# Power_MCU.net
KiCad netlist of a schematic drawn in Altium Designer
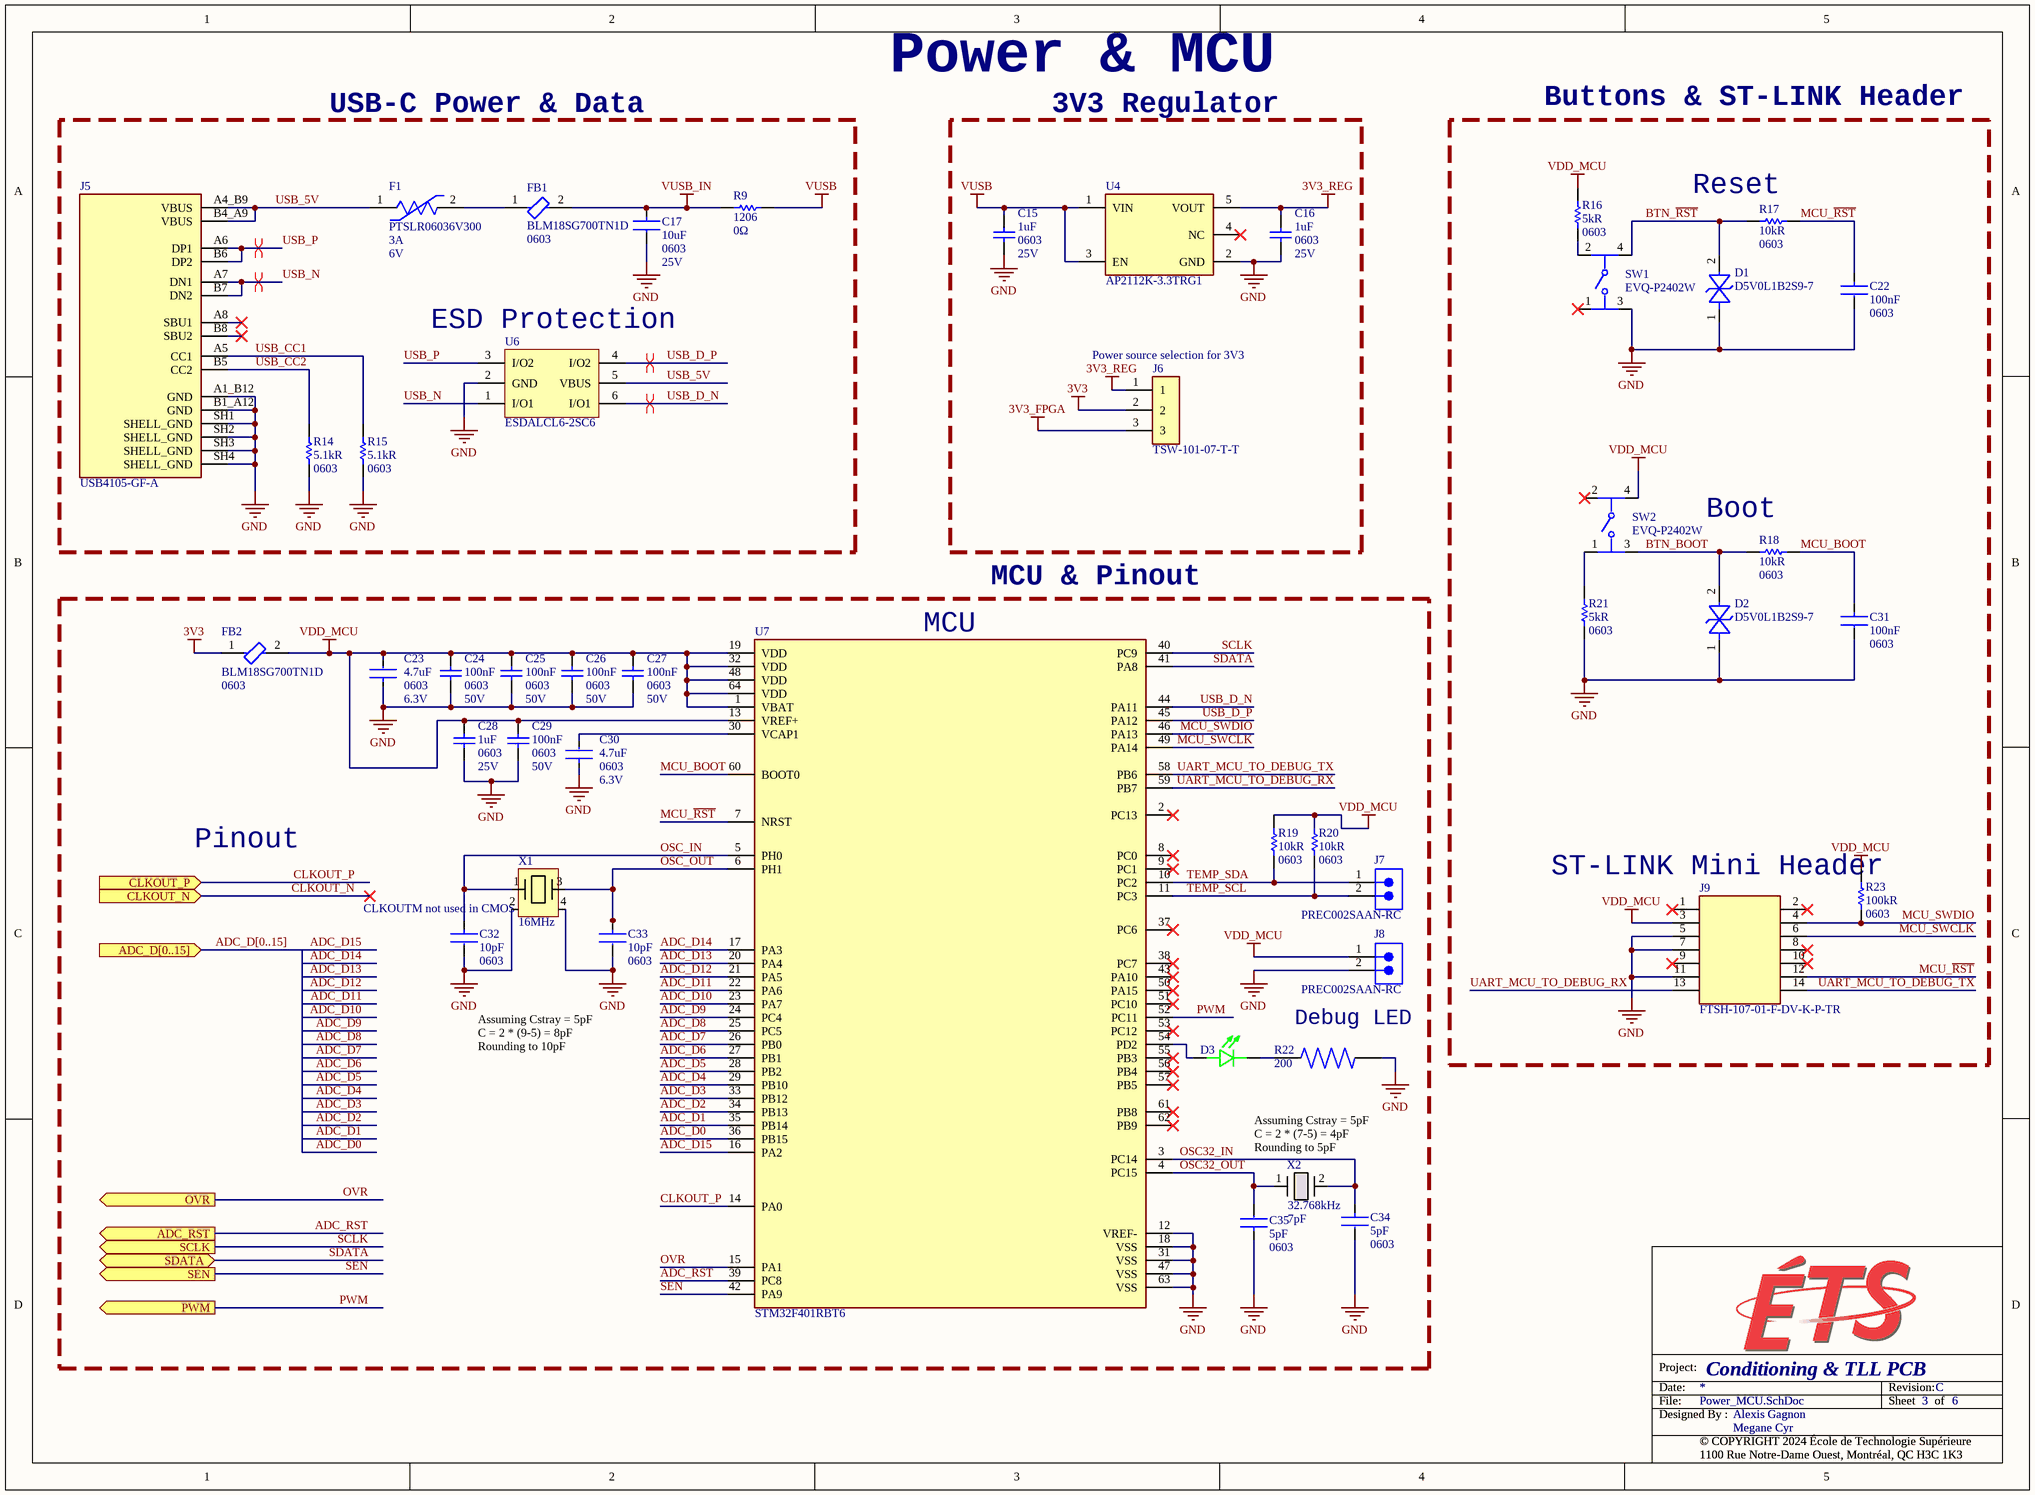
[diagram p0: Power_MCU.SchDoc]

(export (version "E")
  (design (tool "Eeschema 10.0.6"))
  (components
    (comp (ref "C15")
      (value "1uF")
      (footprint "ANTC1608X90N")
      (description "CAP CER 1UF 25V X5R 0603")
      (fields
        (field (name "MANUFACTURER") "Samsung")
        (field (name "MANUFACTURER PART NUMBER") "CL10A105KA8NNNC")
        (field (name "CASE/PACKAGE") "0603")
        (field (name "RATED DC VOLTAGE (URDC)") "25V")
      )
      (libsource (lib "ETS_Library") (part "CL10A105KA8NNNC"))
    )
    (comp (ref "C16")
      (value "1uF")
      (footprint "ANTC1608X90N")
      (description "CAP CER 1UF 25V X5R 0603")
      (fields
        (field (name "MANUFACTURER") "Samsung")
        (field (name "MANUFACTURER PART NUMBER") "CL10A105KA8NNNC")
        (field (name "CASE/PACKAGE") "0603")
        (field (name "RATED DC VOLTAGE (URDC)") "25V")
      )
      (libsource (lib "ETS_Library") (part "CL10A105KA8NNNC"))
    )
    (comp (ref "C17")
      (value "10uF")
      (footprint "BMS:C0603")
      (description "CAP CER 10UF 25V X5R 0603")
      (fields
        (field (name "TOLERANCE") "20%")
        (field (name "MANUFACTURER") "Murata")
        (field (name "CASE/PACKAGE") "0603")
        (field (name "VOLTAGE") "25V")
      )
      (libsource (lib "BMS") (part "GRM188R61E106MA73D"))
    )
    (comp (ref "C22")
      (value "100nF")
      (footprint "BMS:C0603-V2")
      (description "CAP CER 100NF 100V X8L 0603")
      (fields
        (field (name "MANUFACTURER") "Samsung")
        (field (name "MANUFACTURER PART NUMBER") "CL10E104KC8VPNC")
        (field (name "CASE") "0603")
      )
      (libsource (lib "BMS") (part "CL10E104KC8VPNC"))
    )
    (comp (ref "C23")
      (value "4.7uF")
      (footprint "FP-C0603-CG-IPC_B")
      (description "CAP CER 4.7UF 6.3V X5R 0603")
      (fields
        (field (name "PACKAGE") "0603")
        (field (name "TOLERANCE") "10%")
        (field (name "MANUFACTURER") "Kemet")
        (field (name "VOLTAGE RATING") "6.3V")
      )
      (libsource (lib "ETS_Library") (part "CMP-2006-02256-2"))
    )
    (comp (ref "C24")
      (value "100nF")
      (footprint "ANTC1608X90N")
      (description "CAP CER 0.1UF 50V X7R 0603")
      (fields
        (field (name "MANUFACTURER") "Samsung")
        (field (name "MANUFACTURER PART NUMBER") "CL10B104KB8NNWC")
        (field (name "CASE/PACKAGE") "0603")
        (field (name "VOLTAGE RATING") "50V")
      )
      (libsource (lib "ETS_Library") (part "CL10B104KB8NNWC"))
    )
    (comp (ref "C25")
      (value "100nF")
      (footprint "ANTC1608X90N")
      (description "CAP CER 0.1UF 50V X7R 0603")
      (fields
        (field (name "MANUFACTURER") "Samsung")
        (field (name "MANUFACTURER PART NUMBER") "CL10B104KB8NNWC")
        (field (name "CASE/PACKAGE") "0603")
        (field (name "VOLTAGE RATING") "50V")
      )
      (libsource (lib "ETS_Library") (part "CL10B104KB8NNWC"))
    )
    (comp (ref "C26")
      (value "100nF")
      (footprint "ANTC1608X90N")
      (description "CAP CER 0.1UF 50V X7R 0603")
      (fields
        (field (name "MANUFACTURER") "Samsung")
        (field (name "MANUFACTURER PART NUMBER") "CL10B104KB8NNWC")
        (field (name "CASE/PACKAGE") "0603")
        (field (name "VOLTAGE RATING") "50V")
      )
      (libsource (lib "ETS_Library") (part "CL10B104KB8NNWC"))
    )
    (comp (ref "C27")
      (value "100nF")
      (footprint "ANTC1608X90N")
      (description "CAP CER 0.1UF 50V X7R 0603")
      (fields
        (field (name "MANUFACTURER") "Samsung")
        (field (name "MANUFACTURER PART NUMBER") "CL10B104KB8NNWC")
        (field (name "CASE/PACKAGE") "0603")
        (field (name "VOLTAGE RATING") "50V")
      )
      (libsource (lib "ETS_Library") (part "CL10B104KB8NNWC"))
    )
    (comp (ref "C28")
      (value "1uF")
      (footprint "ANTC1608X90N")
      (description "CAP CER 1UF 25V X5R 0603")
      (fields
        (field (name "MANUFACTURER") "Samsung")
        (field (name "MANUFACTURER PART NUMBER") "CL10A105KA8NNNC")
        (field (name "CASE/PACKAGE") "0603")
        (field (name "RATED DC VOLTAGE (URDC)") "25V")
      )
      (libsource (lib "ETS_Library") (part "CL10A105KA8NNNC"))
    )
    (comp (ref "C29")
      (value "100nF")
      (footprint "ANTC1608X90N")
      (description "CAP CER 0.1UF 50V X7R 0603")
      (fields
        (field (name "MANUFACTURER") "Samsung")
        (field (name "MANUFACTURER PART NUMBER") "CL10B104KB8NNWC")
        (field (name "CASE/PACKAGE") "0603")
        (field (name "VOLTAGE RATING") "50V")
      )
      (libsource (lib "ETS_Library") (part "CL10B104KB8NNWC"))
    )
    (comp (ref "C30")
      (value "4.7uF")
      (footprint "FP-C0603-CG-IPC_B")
      (description "CAP CER 4.7UF 6.3V X5R 0603")
      (fields
        (field (name "PACKAGE") "0603")
        (field (name "TOLERANCE") "10%")
        (field (name "MANUFACTURER") "Kemet")
        (field (name "VOLTAGE RATING") "6.3V")
      )
      (libsource (lib "ETS_Library") (part "CMP-2006-02256-2"))
    )
    (comp (ref "C31")
      (value "100nF")
      (footprint "BMS:C0603-V2")
      (description "CAP CER 100NF 100V X8L 0603")
      (fields
        (field (name "MANUFACTURER") "Samsung")
        (field (name "MANUFACTURER PART NUMBER") "CL10E104KC8VPNC")
        (field (name "CASE") "0603")
      )
      (libsource (lib "BMS") (part "CL10E104KC8VPNC"))
    )
    (comp (ref "C32")
      (value "10pF")
      (footprint "BMS:C0603-V2")
      (description "CAP CER 10PF 100V C0G/NP0 0603")
      (fields
        (field (name "MANUFACTURER") "Murata")
        (field (name "MANUFACTURER PART NUMBER") "GCM1885C2A100JA16D")
        (field (name "CASE/PACKAGE") "0603")
      )
      (libsource (lib "BMS") (part "GCM1885C2A100JA16D"))
    )
    (comp (ref "C33")
      (value "10pF")
      (footprint "BMS:C0603-V2")
      (description "CAP CER 10PF 100V C0G/NP0 0603")
      (fields
        (field (name "MANUFACTURER") "Murata")
        (field (name "MANUFACTURER PART NUMBER") "GCM1885C2A100JA16D")
        (field (name "CASE/PACKAGE") "0603")
      )
      (libsource (lib "BMS") (part "GCM1885C2A100JA16D"))
    )
    (comp (ref "C34")
      (value "5pF")
      (footprint "C0603-V2")
      (description "CAP CER 5PF 100V C0G/NP0 0603")
      (fields
        (field (name "MANUFACTURER") "Walsin Technologies")
        (field (name "MANUFACTURER PART NUMBER") "0603N5R0B101CT")
        (field (name "CASE") "0603")
      )
      (libsource (lib "BMS") (part "0603N5R0B101CT"))
    )
    (comp (ref "C35")
      (value "5pF")
      (footprint "C0603-V2")
      (description "CAP CER 5PF 100V C0G/NP0 0603")
      (fields
        (field (name "MANUFACTURER") "Walsin Technologies")
        (field (name "MANUFACTURER PART NUMBER") "0603N5R0B101CT")
        (field (name "CASE") "0603")
      )
      (libsource (lib "BMS") (part "0603N5R0B101CT"))
    )
    (comp (ref "D1")
      (value "D5V0L1B2S9-7")
      (footprint "SOD923_DIO")
      (description "TVS DIODE 5VWM 14VC SOD923")
      (fields (field (name "MANUFACTURER") "Diodes"))
      (libsource (lib "BMS") (part "D5V0L1B2S9-7"))
    )
    (comp (ref "D2")
      (value "D5V0L1B2S9-7")
      (footprint "SOD923_DIO")
      (description "TVS DIODE 5VWM 14VC SOD923")
      (fields (field (name "MANUFACTURER") "Diodes"))
      (libsource (lib "BMS") (part "D5V0L1B2S9-7"))
    )
    (comp (ref "D3")
      (value "LTST-C170GKT")
      (footprint "LED_LTST-C170GKT_LTO")
      (description "LED GREEN CLEAR SMD")
      (fields (field (name "COPYRIGHT") "Copyright (C) 2025 Ultra Librarian. All rights reserved."))
      (libsource (lib "ETS_Library") (part "LTST-C170GKT"))
    )
    (comp (ref "F1")
      (value "PTSLR06036V300")
      (footprint "BMS:FP-PTSLR06036V300-MFG")
      (description "PTC RESET FUSE 3A 6V 0603")
      (fields
        (field (name "MANUFACTURER") "Eaton")
        (field (name "CURRENT HOLD") "3A")
        (field (name "VOLTAGE") "6V")
      )
      (libsource (lib "BMS") (part "PTSLR06036V300"))
    )
    (comp (ref "FB1")
      (value "BLM18SG700TN1D")
      (footprint "BMS:BLM18SG700TN1D-MFG")
      (description "FERRITE BEAD 70 OHM 0603 1LN")
      (fields
        (field (name "TOLERANCE") "25%")
        (field (name "MANUFACTURER") "Murata")
        (field (name "CASE CODE (IMPERIAL)") "0603")
      )
      (libsource (lib "BMS") (part "BLM18SG700TN1D"))
    )
    (comp (ref "FB2")
      (value "BLM18SG700TN1D")
      (footprint "BMS:BLM18SG700TN1D-MFG")
      (description "FERRITE BEAD 70 OHM 0603 1LN")
      (fields
        (field (name "TOLERANCE") "25%")
        (field (name "MANUFACTURER") "Murata")
        (field (name "CASE CODE (IMPERIAL)") "0603")
      )
      (libsource (lib "BMS") (part "BLM18SG700TN1D"))
    )
    (comp (ref "J5")
      (value "USB4105-GF-A")
      (footprint "BMS:GCT_USB4105-GF-A")
      (description "CONN RCP USB2.0 TYP C 24P SMD RA")
      (fields (field (name "MANUFACTURER") "Global Connector Technology"))
      (libsource (lib "BMS") (part "USB4105-GF-A"))
    )
    (comp (ref "J6")
      (value "TSW-101-07-T-T")
      (footprint "SAMTEC_TSW-101-07-T-T")
      (fields (field (name "MF") "Samtec"))
      (libsource (lib "ETS_Library") (part "TSW-101-07-T-T"))
    )
    (comp (ref "J7")
      (value "PREC002SAAN-RC")
      (footprint "CONN_PREC002SAAN-RC_SUL")
      (description "CONN HEADER .100 SNGL STR 2POS")
      (fields (field (name "MANUFACTURER") "Sullins"))
      (libsource (lib "ETS_Library") (part "PREC002SAAN-RC"))
    )
    (comp (ref "J8")
      (value "PREC002SAAN-RC")
      (footprint "CONN_PREC002SAAN-RC_SUL")
      (description "CONN HEADER .100 SNGL STR 2POS")
      (fields (field (name "MANUFACTURER") "Sullins"))
      (libsource (lib "ETS_Library") (part "PREC002SAAN-RC"))
    )
    (comp (ref "J9")
      (value "FTSH-107-01-F-DV-K-P-TR")
      (footprint "BMS:SAMTEC_FTSH-107-01-F-DV-K-P-TR")
      (description "CONN HEADER SMD 14POS 1.27MM")
      (fields (field (name "MANUFACTURER") "Samtec"))
      (libsource (lib "BMS") (part "FTSH-107-01-F-DV-K-P-TR"))
    )
    (comp (ref "R9")
      (value "RC1206JR-070RL")
      (footprint "BMS:R1206")
      (description "RES 0 OHM JUMPER 1/4W 1206")
      (fields
        (field (name "MANUFACTURER") "YAGEO")
        (field (name "OCTOPART") "https://octopart.com/rc1206jr-070rl-yageo-40025601")
        (field (name "CASE/PACKAGE") "1206")
        (field (name "RESISTANCE") "0Ω")
      )
      (libsource (lib "BMS") (part "RC1206JR-070RL"))
    )
    (comp (ref "R14")
      (value "5.1kR")
      (footprint "BMS:R0603")
      (description "RES 5.1K OHM 1% 1/10W 0603")
      (fields
        (field (name "MANUFACTURER") "Yageo")
        (field (name "PART NUMBER") "RC0603FR-075K1L")
        (field (name "CASE/PACKAGE") "0603")
      )
      (libsource (lib "BMS") (part "RC0603FR-075K1L"))
    )
    (comp (ref "R15")
      (value "5.1kR")
      (footprint "BMS:R0603")
      (description "RES 5.1K OHM 1% 1/10W 0603")
      (fields
        (field (name "MANUFACTURER") "Yageo")
        (field (name "PART NUMBER") "RC0603FR-075K1L")
        (field (name "CASE/PACKAGE") "0603")
      )
      (libsource (lib "BMS") (part "RC0603FR-075K1L"))
    )
    (comp (ref "R16")
      (value "5kR")
      (footprint "BMS:R0603")
      (description "RES 5K OHM 0.1% 1/10W 0603")
      (fields
        (field (name "MANUFACTURER") "Yageo")
        (field (name "MANUFACTURER PART NUMBER") "RT0603BRE075KL")
        (field (name "CASE") "0603")
      )
      (libsource (lib "BMS") (part "RT0603BRE075KL"))
    )
    (comp (ref "R17")
      (value "10kR")
      (footprint "BMS:R0603")
      (description "10 kOhms ±1% 0.1W, 1/10W Chip Resistor 0603 (1608 Metric) Moisture Resistant Thick Film")
      (fields
        (field (name "MANUFACTURER") "Yageo")
        (field (name "MANUFACTURER PART NUMBER") "RC0603FR-0710KL")
        (field (name "CASE/PACKAGE") "0603")
      )
      (libsource (lib "BMS") (part "RC0603FR-0710KL"))
    )
    (comp (ref "R18")
      (value "10kR")
      (footprint "BMS:R0603")
      (description "10 kOhms ±1% 0.1W, 1/10W Chip Resistor 0603 (1608 Metric) Moisture Resistant Thick Film")
      (fields
        (field (name "MANUFACTURER") "Yageo")
        (field (name "MANUFACTURER PART NUMBER") "RC0603FR-0710KL")
        (field (name "CASE/PACKAGE") "0603")
      )
      (libsource (lib "BMS") (part "RC0603FR-0710KL"))
    )
    (comp (ref "R19")
      (value "10kR")
      (footprint "BMS:R0603")
      (description "10 kOhms ±1% 0.1W, 1/10W Chip Resistor 0603 (1608 Metric) Moisture Resistant Thick Film")
      (fields
        (field (name "MANUFACTURER") "Yageo")
        (field (name "MANUFACTURER PART NUMBER") "RC0603FR-0710KL")
        (field (name "CASE/PACKAGE") "0603")
      )
      (libsource (lib "BMS") (part "RC0603FR-0710KL"))
    )
    (comp (ref "R20")
      (value "10kR")
      (footprint "BMS:R0603")
      (description "10 kOhms ±1% 0.1W, 1/10W Chip Resistor 0603 (1608 Metric) Moisture Resistant Thick Film")
      (fields
        (field (name "MANUFACTURER") "Yageo")
        (field (name "MANUFACTURER PART NUMBER") "RC0603FR-0710KL")
        (field (name "CASE/PACKAGE") "0603")
      )
      (libsource (lib "BMS") (part "RC0603FR-0710KL"))
    )
    (comp (ref "R21")
      (value "5kR")
      (footprint "BMS:R0603")
      (description "RES 5K OHM 0.1% 1/10W 0603")
      (fields
        (field (name "MANUFACTURER") "Yageo")
        (field (name "MANUFACTURER PART NUMBER") "RT0603BRE075KL")
        (field (name "CASE") "0603")
      )
      (libsource (lib "BMS") (part "RT0603BRE075KL"))
    )
    (comp (ref "R22")
      (value "200")
      (footprint "RESC1608X55N")
      (description "RES 200 OHM 5% 1/10W 0603")
      (fields (field (name "MF") "Yageo") (field (name "MP") "RC0603JR-07200RL"))
      (libsource (lib "ETS_Library") (part "RC0603JR-07200RL"))
    )
    (comp (ref "R23")
      (value "100kR")
      (footprint "BMS:R0603")
      (description "RES 100K OHM 1% 1/10W 0603")
      (fields
        (field (name "MANUFACTURER") "Yageo")
        (field (name "MANUFACTURER PART NUMBER") "RC0603FR-07100KL")
        (field (name "CASE/PACKAGE") "0603")
      )
      (libsource (lib "BMS") (part "RC0603FR-07100KL"))
    )
    (comp (ref "SW1")
      (value "EVQ-P2402W")
      (footprint "FP-EVQ-P2402W-MFG")
      (description "SWITCH TACTILE SPST-NO 0.02A 15V")
      (fields (field (name "MANUFACTURER") "Panasonic"))
      (libsource (lib "BMS") (part "EVQ-P2402W"))
    )
    (comp (ref "SW2")
      (value "EVQ-P2402W")
      (footprint "FP-EVQ-P2402W-MFG")
      (description "SWITCH TACTILE SPST-NO 0.02A 15V")
      (fields (field (name "MANUFACTURER") "Panasonic"))
      (libsource (lib "BMS") (part "EVQ-P2402W"))
    )
    (comp (ref "U4")
      (value "AP2112K-3.3TRG1")
      (footprint "FP-SOT25-MFG")
      (description "IC REG LINEAR 3.3V 600MA SOT25")
      (libsource (lib "ETS_Library") (part "AP2112K-3.3TRG1"))
    )
    (comp (ref "U6")
      (value "ESDALCL6-2SC6")
      (footprint "BMS:ESDALCL6-2SC6")
      (description "TVS DIODE 3VWM 17VC SOT23-6")
      (fields (field (name "MANUFACTURER") "STMicroelectronics"))
      (libsource (lib "BMS") (part "ESDALCL6-2SC6"))
    )
    (comp (ref "U7")
      (value "STM32F401RBT6")
      (footprint "QFP50P1200X1200X160-64N")
      (fields (field (name "MF") "STMicroelectronics"))
      (libsource (lib "ETS_Library") (part "STM32F401RBT6"))
    )
    (comp (ref "X1")
      (value "16MHz")
      (footprint "FP-TSX-3225-MFG")
      (description "CRYSTAL 16.0000MHZ 9PF SMD")
      (fields
        (field (name "MANUFACTURER") "Epson")
        (field (name "MANUFACTURER PART NUMBER") "TSX-3225 16.0000MF18X-AC0")
      )
      (libsource (lib "BMS") (part "TSX-3225 16.0000MF18X-AC0"))
    )
    (comp (ref "X2")
      (value "32.768kHz")
      (footprint "XTAL_SC32S-7PF20PPM_EPS")
      (description "CRYSTAL 32.7680KHZ 7PF SMD")
      (fields
        (field (name "MANUFACTURER") "Seiko")
        (field (name "MANUFACTURER PART NUMBER") "SC32S-7PF20PPM")
        (field (name "LOAD CAPACITANCE") "7pF")
      )
      (libsource (lib "BMS") (part "SC32S-7PF20PPM"))
    )
  )
  (nets
    (net (code "1") (name "/ADC_D0") (class "Default")
      (node (ref "U7") (pin "36") (pinfunction "PB15_36") (pintype "passive"))
    )
    (net (code "2") (name "/ADC_D1") (class "Default")
      (node (ref "U7") (pin "35") (pinfunction "PB14_35") (pintype "passive"))
    )
    (net (code "3") (name "/ADC_D2") (class "Default")
      (node (ref "U7") (pin "34") (pinfunction "PB13_34") (pintype "passive"))
    )
    (net (code "4") (name "/ADC_D3") (class "Default")
      (node (ref "U7") (pin "33") (pinfunction "PB12_33") (pintype "passive"))
    )
    (net (code "5") (name "/ADC_D4") (class "Default")
      (node (ref "U7") (pin "29") (pinfunction "PB10_29") (pintype "passive"))
    )
    (net (code "6") (name "/ADC_D5") (class "Default")
      (node (ref "U7") (pin "28") (pinfunction "PB2_28") (pintype "passive"))
    )
    (net (code "7") (name "/ADC_D6") (class "Default")
      (node (ref "U7") (pin "27") (pinfunction "PB1_27") (pintype "passive"))
    )
    (net (code "8") (name "/ADC_D7") (class "Default")
      (node (ref "U7") (pin "26") (pinfunction "PB0_26") (pintype "passive"))
    )
    (net (code "9") (name "/ADC_D8") (class "Default")
      (node (ref "U7") (pin "25") (pinfunction "PC5_25") (pintype "passive"))
    )
    (net (code "10") (name "/ADC_D9") (class "Default")
      (node (ref "U7") (pin "24") (pinfunction "PC4_24") (pintype "passive"))
    )
    (net (code "11") (name "/ADC_D10") (class "Default")
      (node (ref "U7") (pin "23") (pinfunction "PA7_23") (pintype "passive"))
    )
    (net (code "12") (name "/ADC_D11") (class "Default")
      (node (ref "U7") (pin "22") (pinfunction "PA6_22") (pintype "passive"))
    )
    (net (code "13") (name "/ADC_D12") (class "Default")
      (node (ref "U7") (pin "21") (pinfunction "PA5_21") (pintype "passive"))
    )
    (net (code "14") (name "/ADC_D13") (class "Default")
      (node (ref "U7") (pin "20") (pinfunction "PA4_20") (pintype "passive"))
    )
    (net (code "15") (name "/ADC_D14") (class "Default")
      (node (ref "U7") (pin "17") (pinfunction "PA3_17") (pintype "passive"))
    )
    (net (code "16") (name "/ADC_D15") (class "Default")
      (node (ref "U7") (pin "16") (pinfunction "PA2_16") (pintype "passive"))
    )
    (net (code "18") (name "/ADC_RST") (class "Default")
      (node (ref "U7") (pin "39") (pinfunction "PC8_39") (pintype "passive"))
    )
    (net (code "19") (name "/BTN_BOOT") (class "Default")
      (node (ref "D2") (pin "2") (pinfunction "2_2") (pintype "passive"))
      (node (ref "R18") (pin "1") (pinfunction "1_1") (pintype "passive"))
      (node (ref "SW2") (pin "3") (pinfunction "3_3") (pintype "passive"))
    )
    (net (code "20") (name "/BTN_~{RST}") (class "Default")
      (node (ref "D1") (pin "2") (pinfunction "2_2") (pintype "passive"))
      (node (ref "R17") (pin "1") (pinfunction "1_1") (pintype "passive"))
      (node (ref "SW1") (pin "4") (pinfunction "4_4") (pintype "passive"))
    )
    (net (code "22") (name "/CLKOUT_P") (class "Default")
      (node (ref "U7") (pin "14") (pinfunction "PA0_14") (pintype "passive"))
    )
    (net (code "23") (name "/MCU_BOOT") (class "Default")
      (node (ref "C31") (pin "1") (pinfunction "1_1") (pintype "passive"))
      (node (ref "R18") (pin "2") (pinfunction "2_2") (pintype "passive"))
      (node (ref "U7") (pin "60") (pinfunction "BOOT0_60") (pintype "passive"))
    )
    (net (code "24") (name "/MCU_SWCLK") (class "Default")
      (node (ref "J9") (pin "6") (pinfunction "6_6") (pintype "passive"))
      (node (ref "U7") (pin "49") (pinfunction "PA14_49") (pintype "passive"))
    )
    (net (code "25") (name "/MCU_SWDIO") (class "Default")
      (node (ref "J9") (pin "4") (pinfunction "4_4") (pintype "passive"))
      (node (ref "R23") (pin "1") (pinfunction "1_1") (pintype "passive"))
      (node (ref "U7") (pin "46") (pinfunction "PA13_46") (pintype "passive"))
    )
    (net (code "26") (name "/MCU_~{RST}") (class "Default")
      (node (ref "C22") (pin "1") (pinfunction "1_1") (pintype "passive"))
      (node (ref "J9") (pin "12") (pinfunction "12_12") (pintype "passive"))
      (node (ref "R17") (pin "2") (pinfunction "2_2") (pintype "passive"))
      (node (ref "U7") (pin "7") (pinfunction "NRST_7") (pintype "passive"))
    )
    (net (code "27") (name "/OSC32_IN") (class "Default")
      (node (ref "C34") (pin "1") (pinfunction "1_1") (pintype "passive"))
      (node (ref "U7") (pin "3") (pinfunction "PC14_3") (pintype "passive"))
      (node (ref "X2") (pin "2") (pinfunction "2_2") (pintype "passive"))
    )
    (net (code "28") (name "/OSC32_OUT") (class "Default")
      (node (ref "C35") (pin "2") (pinfunction "2_2") (pintype "passive"))
      (node (ref "U7") (pin "4") (pinfunction "PC15_4") (pintype "passive"))
      (node (ref "X2") (pin "1") (pinfunction "1_1") (pintype "passive"))
    )
    (net (code "29") (name "/OSC_IN") (class "Default")
      (node (ref "C32") (pin "1") (pinfunction "1_1") (pintype "passive"))
      (node (ref "U7") (pin "5") (pinfunction "PH0_5") (pintype "passive"))
      (node (ref "X1") (pin "1") (pinfunction "1_1") (pintype "passive"))
    )
    (net (code "30") (name "/OSC_OUT") (class "Default")
      (node (ref "C33") (pin "1") (pinfunction "1_1") (pintype "passive"))
      (node (ref "U7") (pin "6") (pinfunction "PH1_6") (pintype "passive"))
      (node (ref "X1") (pin "3") (pinfunction "3_3") (pintype "passive"))
    )
    (net (code "31") (name "/OVR") (class "Default")
      (node (ref "U7") (pin "15") (pinfunction "PA1_15") (pintype "passive"))
    )
    (net (code "32") (name "/PWM") (class "Default")
      (node (ref "U7") (pin "52") (pinfunction "PC11_52") (pintype "passive"))
    )
    (net (code "33") (name "/SCLK") (class "Default")
      (node (ref "U7") (pin "40") (pinfunction "PC9_40") (pintype "passive"))
    )
    (net (code "34") (name "/SDATA") (class "Default")
      (node (ref "U7") (pin "41") (pinfunction "PA8_41") (pintype "passive"))
    )
    (net (code "35") (name "/SEN") (class "Default")
      (node (ref "U7") (pin "42") (pinfunction "PA9_42") (pintype "passive"))
    )
    (net (code "36") (name "/TEMP_SCL") (class "Default")
      (node (ref "J7") (pin "2") (pinfunction "2_2") (pintype "passive"))
      (node (ref "R20") (pin "1") (pinfunction "1_1") (pintype "passive"))
      (node (ref "U7") (pin "11") (pinfunction "PC3_11") (pintype "passive"))
    )
    (net (code "37") (name "/TEMP_SDA") (class "Default")
      (node (ref "J7") (pin "1") (pinfunction "1_1") (pintype "passive"))
      (node (ref "R19") (pin "1") (pinfunction "1_1") (pintype "passive"))
      (node (ref "U7") (pin "10") (pinfunction "PC2_10") (pintype "passive"))
    )
    (net (code "38") (name "/UART_MCU_TO_DEBUG_RX") (class "Default")
      (node (ref "J9") (pin "13") (pinfunction "13_13") (pintype "passive"))
      (node (ref "U7") (pin "59") (pinfunction "PB7_59") (pintype "passive"))
    )
    (net (code "39") (name "/UART_MCU_TO_DEBUG_TX") (class "Default")
      (node (ref "J9") (pin "14") (pinfunction "14_14") (pintype "passive"))
      (node (ref "U7") (pin "58") (pinfunction "PB6_58") (pintype "passive"))
    )
    (net (code "40") (name "/USB_5V") (class "Default")
      (node (ref "F1") (pin "1") (pinfunction "1_1") (pintype "passive"))
      (node (ref "J5") (pin "A4_B9") (pinfunction "VBUS_A4_B9") (pintype "passive"))
      (node (ref "J5") (pin "B4_A9") (pinfunction "VBUS_B4_A9") (pintype "passive"))
      (node (ref "U6") (pin "5") (pinfunction "VBUS_5") (pintype "passive"))
    )
    (net (code "41") (name "/USB_CC1") (class "Default")
      (node (ref "J5") (pin "A5") (pinfunction "CC1_A5") (pintype "passive"))
      (node (ref "R15") (pin "2") (pinfunction "2_2") (pintype "passive"))
    )
    (net (code "42") (name "/USB_CC2") (class "Default")
      (node (ref "J5") (pin "B5") (pinfunction "CC2_B5") (pintype "passive"))
      (node (ref "R14") (pin "2") (pinfunction "2_2") (pintype "passive"))
    )
    (net (code "43") (name "/USB_D_N") (class "Default")
      (node (ref "U6") (pin "6") (pinfunction "I/O1_6") (pintype "passive"))
      (node (ref "U7") (pin "44") (pinfunction "PA11_44") (pintype "passive"))
    )
    (net (code "44") (name "/USB_D_P") (class "Default")
      (node (ref "U6") (pin "4") (pinfunction "I/O2_4") (pintype "passive"))
      (node (ref "U7") (pin "45") (pinfunction "PA12_45") (pintype "passive"))
    )
    (net (code "45") (name "/USB_N") (class "Default")
      (node (ref "J5") (pin "A7") (pinfunction "DN1_A7") (pintype "passive"))
      (node (ref "J5") (pin "B7") (pinfunction "DN2_B7") (pintype "passive"))
      (node (ref "U6") (pin "1") (pinfunction "I/O1_1") (pintype "passive"))
    )
    (net (code "46") (name "/USB_P") (class "Default")
      (node (ref "J5") (pin "A6") (pinfunction "DP1_A6") (pintype "passive"))
      (node (ref "J5") (pin "B6") (pinfunction "DP2_B6") (pintype "passive"))
      (node (ref "U6") (pin "3") (pinfunction "I/O2_3") (pintype "passive"))
    )
    (net (code "47") (name "3V3") (class "Default")
      (node (ref "FB2") (pin "1") (pinfunction "1_1") (pintype "passive"))
      (node (ref "J6") (pin "2") (pinfunction "2_2") (pintype "passive"))
    )
    (net (code "48") (name "3V3_FPGA") (class "Default")
      (node (ref "J6") (pin "3") (pinfunction "3_3") (pintype "passive"))
    )
    (net (code "49") (name "3V3_REG") (class "Default")
      (node (ref "C16") (pin "2") (pinfunction "2_2") (pintype "passive"))
      (node (ref "J6") (pin "1") (pinfunction "1_1") (pintype "passive"))
      (node (ref "U4") (pin "5") (pinfunction "VOUT_5") (pintype "power_in"))
    )
    (net (code "50") (name "GND") (class "Default")
      (node (ref "C15") (pin "1") (pinfunction "1_1") (pintype "passive"))
      (node (ref "C16") (pin "1") (pinfunction "1_1") (pintype "passive"))
      (node (ref "C17") (pin "2") (pinfunction "2_2") (pintype "passive"))
      (node (ref "C22") (pin "2") (pinfunction "2_2") (pintype "passive"))
      (node (ref "C23") (pin "1") (pinfunction "1_1") (pintype "passive"))
      (node (ref "C24") (pin "2") (pinfunction "2_2") (pintype "passive"))
      (node (ref "C25") (pin "2") (pinfunction "2_2") (pintype "passive"))
      (node (ref "C26") (pin "2") (pinfunction "2_2") (pintype "passive"))
      (node (ref "C27") (pin "2") (pinfunction "2_2") (pintype "passive"))
      (node (ref "C28") (pin "1") (pinfunction "1_1") (pintype "passive"))
      (node (ref "C29") (pin "2") (pinfunction "2_2") (pintype "passive"))
      (node (ref "C30") (pin "1") (pinfunction "1_1") (pintype "passive"))
      (node (ref "C31") (pin "2") (pinfunction "2_2") (pintype "passive"))
      (node (ref "C32") (pin "2") (pinfunction "2_2") (pintype "passive"))
      (node (ref "C33") (pin "2") (pinfunction "2_2") (pintype "passive"))
      (node (ref "C34") (pin "2") (pinfunction "2_2") (pintype "passive"))
      (node (ref "C35") (pin "1") (pinfunction "1_1") (pintype "passive"))
      (node (ref "D1") (pin "1") (pinfunction "1_1") (pintype "passive"))
      (node (ref "D2") (pin "1") (pinfunction "1_1") (pintype "passive"))
      (node (ref "J5") (pin "A1_B12") (pinfunction "GND_A1_B12") (pintype "passive"))
      (node (ref "J5") (pin "B1_A12") (pinfunction "GND_B1_A12") (pintype "passive"))
      (node (ref "J5") (pin "SH1") (pinfunction "SHELL_GND_SH1") (pintype "passive"))
      (node (ref "J5") (pin "SH2") (pinfunction "SHELL_GND_SH2") (pintype "passive"))
      (node (ref "J5") (pin "SH3") (pinfunction "SHELL_GND_SH3") (pintype "passive"))
      (node (ref "J5") (pin "SH4") (pinfunction "SHELL_GND_SH4") (pintype "passive"))
      (node (ref "J8") (pin "2") (pinfunction "2_2") (pintype "passive"))
      (node (ref "J9") (pin "11") (pinfunction "11_11") (pintype "passive"))
      (node (ref "J9") (pin "5") (pinfunction "5_5") (pintype "passive"))
      (node (ref "J9") (pin "7") (pinfunction "7_7") (pintype "passive"))
      (node (ref "R14") (pin "1") (pinfunction "1_1") (pintype "passive"))
      (node (ref "R15") (pin "1") (pinfunction "1_1") (pintype "passive"))
      (node (ref "R21") (pin "1") (pinfunction "1_1") (pintype "passive"))
      (node (ref "R22") (pin "2") (pinfunction "2_2") (pintype "passive"))
      (node (ref "SW1") (pin "3") (pinfunction "3_3") (pintype "passive"))
      (node (ref "U4") (pin "2") (pinfunction "GND_2") (pintype "power_in"))
      (node (ref "U6") (pin "2") (pinfunction "GND_2") (pintype "passive"))
      (node (ref "U7") (pin "12") (pinfunction "VREF-_12") (pintype "passive"))
      (node (ref "U7") (pin "18") (pinfunction "VSS_18") (pintype "passive"))
      (node (ref "U7") (pin "31") (pinfunction "VSS_31") (pintype "passive"))
      (node (ref "U7") (pin "47") (pinfunction "VSS_47") (pintype "passive"))
      (node (ref "U7") (pin "63") (pinfunction "VSS_63") (pintype "passive"))
      (node (ref "X1") (pin "2") (pinfunction "2_2") (pintype "passive"))
      (node (ref "X1") (pin "4") (pinfunction "4_4") (pintype "passive"))
    )
    (net (code "51") (name "Net-(D3-Pad1)") (class "Default")
      (node (ref "D3") (pin "1") (pinfunction "1_1") (pintype "passive"))
      (node (ref "R22") (pin "1") (pinfunction "1_1") (pintype "passive"))
    )
    (net (code "52") (name "Net-(F1-Pad2)") (class "Default")
      (node (ref "F1") (pin "2") (pinfunction "2_2") (pintype "passive"))
      (node (ref "FB1") (pin "1") (pinfunction "1_1") (pintype "passive"))
    )
    (net (code "53") (name "Net-(R16-Pad1)") (class "Default")
      (node (ref "R16") (pin "1") (pinfunction "1_1") (pintype "passive"))
      (node (ref "SW1") (pin "2") (pinfunction "2_2") (pintype "passive"))
    )
    (net (code "54") (name "Net-(R21-Pad2)") (class "Default")
      (node (ref "R21") (pin "2") (pinfunction "2_2") (pintype "passive"))
      (node (ref "SW2") (pin "1") (pinfunction "1_1") (pintype "passive"))
    )
    (net (code "55") (name "Net-(U7-PD2)") (class "Default")
      (node (ref "D3") (pin "2") (pinfunction "2_2") (pintype "passive"))
      (node (ref "U7") (pin "54") (pinfunction "PD2_54") (pintype "passive"))
    )
    (net (code "56") (name "Net-(U7-VCAP1)") (class "Default")
      (node (ref "C30") (pin "2") (pinfunction "2_2") (pintype "passive"))
      (node (ref "U7") (pin "30") (pinfunction "VCAP1_30") (pintype "passive"))
    )
    (net (code "57") (name "VDD_MCU") (class "Default")
      (node (ref "C23") (pin "2") (pinfunction "2_2") (pintype "passive"))
      (node (ref "C24") (pin "1") (pinfunction "1_1") (pintype "passive"))
      (node (ref "C25") (pin "1") (pinfunction "1_1") (pintype "passive"))
      (node (ref "C26") (pin "1") (pinfunction "1_1") (pintype "passive"))
      (node (ref "C27") (pin "1") (pinfunction "1_1") (pintype "passive"))
      (node (ref "C28") (pin "2") (pinfunction "2_2") (pintype "passive"))
      (node (ref "C29") (pin "1") (pinfunction "1_1") (pintype "passive"))
      (node (ref "FB2") (pin "2") (pinfunction "2_2") (pintype "passive"))
      (node (ref "J8") (pin "1") (pinfunction "1_1") (pintype "passive"))
      (node (ref "J9") (pin "3") (pinfunction "3_3") (pintype "passive"))
      (node (ref "R16") (pin "2") (pinfunction "2_2") (pintype "passive"))
      (node (ref "R19") (pin "2") (pinfunction "2_2") (pintype "passive"))
      (node (ref "R20") (pin "2") (pinfunction "2_2") (pintype "passive"))
      (node (ref "R23") (pin "2") (pinfunction "2_2") (pintype "passive"))
      (node (ref "SW2") (pin "4") (pinfunction "4_4") (pintype "passive"))
      (node (ref "U7") (pin "1") (pinfunction "VBAT_1") (pintype "passive"))
      (node (ref "U7") (pin "13") (pinfunction "VREF+_13") (pintype "passive"))
      (node (ref "U7") (pin "19") (pinfunction "VDD_19") (pintype "passive"))
      (node (ref "U7") (pin "32") (pinfunction "VDD_32") (pintype "passive"))
      (node (ref "U7") (pin "48") (pinfunction "VDD_48") (pintype "passive"))
      (node (ref "U7") (pin "64") (pinfunction "VDD_64") (pintype "passive"))
    )
    (net (code "58") (name "VUSB") (class "Default")
      (node (ref "C15") (pin "2") (pinfunction "2_2") (pintype "passive"))
      (node (ref "R9") (pin "2") (pinfunction "2_2") (pintype "passive"))
      (node (ref "U4") (pin "1") (pinfunction "VIN_1") (pintype "power_in"))
      (node (ref "U4") (pin "3") (pinfunction "EN_3") (pintype "passive"))
    )
    (net (code "59") (name "VUSB_IN") (class "Default")
      (node (ref "C17") (pin "1") (pinfunction "1_1") (pintype "passive"))
      (node (ref "FB1") (pin "2") (pinfunction "2_2") (pintype "passive"))
      (node (ref "R9") (pin "1") (pinfunction "1_1") (pintype "passive"))
    )
    (net (code "60") (name "unconnected-(J5-SBU1-PadA8)") (class "Default")
      (node (ref "J5") (pin "A8") (pinfunction "SBU1_A8") (pintype "passive+no_connect"))
    )
    (net (code "61") (name "unconnected-(J5-SBU2-PadB8)") (class "Default")
      (node (ref "J5") (pin "B8") (pinfunction "SBU2_B8") (pintype "passive+no_connect"))
    )
    (net (code "62") (name "unconnected-(J9-Pad1)") (class "Default")
      (node (ref "J9") (pin "1") (pinfunction "1_1") (pintype "passive+no_connect"))
    )
    (net (code "63") (name "unconnected-(J9-Pad2)") (class "Default")
      (node (ref "J9") (pin "2") (pinfunction "2_2") (pintype "passive+no_connect"))
    )
    (net (code "64") (name "unconnected-(J9-Pad8)") (class "Default")
      (node (ref "J9") (pin "8") (pinfunction "8_8") (pintype "passive+no_connect"))
    )
    (net (code "65") (name "unconnected-(J9-Pad9)") (class "Default")
      (node (ref "J9") (pin "9") (pinfunction "9_9") (pintype "passive+no_connect"))
    )
    (net (code "66") (name "unconnected-(J9-Pad10)") (class "Default")
      (node (ref "J9") (pin "10") (pinfunction "10_10") (pintype "passive+no_connect"))
    )
    (net (code "67") (name "unconnected-(SW1-Pad1)") (class "Default")
      (node (ref "SW1") (pin "1") (pinfunction "1_1") (pintype "passive+no_connect"))
    )
    (net (code "68") (name "unconnected-(SW2-Pad2)") (class "Default")
      (node (ref "SW2") (pin "2") (pinfunction "2_2") (pintype "passive+no_connect"))
    )
    (net (code "69") (name "unconnected-(U4-NC-Pad4)") (class "Default")
      (node (ref "U4") (pin "4") (pinfunction "NC_4") (pintype "passive+no_connect"))
    )
    (net (code "70") (name "unconnected-(U7-PA10-Pad43)") (class "Default")
      (node (ref "U7") (pin "43") (pinfunction "PA10_43") (pintype "passive+no_connect"))
    )
    (net (code "71") (name "unconnected-(U7-PA15-Pad50)") (class "Default")
      (node (ref "U7") (pin "50") (pinfunction "PA15_50") (pintype "passive+no_connect"))
    )
    (net (code "72") (name "unconnected-(U7-PB3-Pad55)") (class "Default")
      (node (ref "U7") (pin "55") (pinfunction "PB3_55") (pintype "passive+no_connect"))
    )
    (net (code "73") (name "unconnected-(U7-PB4-Pad56)") (class "Default")
      (node (ref "U7") (pin "56") (pinfunction "PB4_56") (pintype "passive+no_connect"))
    )
    (net (code "74") (name "unconnected-(U7-PB5-Pad57)") (class "Default")
      (node (ref "U7") (pin "57") (pinfunction "PB5_57") (pintype "passive+no_connect"))
    )
    (net (code "75") (name "unconnected-(U7-PB8-Pad61)") (class "Default")
      (node (ref "U7") (pin "61") (pinfunction "PB8_61") (pintype "passive+no_connect"))
    )
    (net (code "76") (name "unconnected-(U7-PB9-Pad62)") (class "Default")
      (node (ref "U7") (pin "62") (pinfunction "PB9_62") (pintype "passive+no_connect"))
    )
    (net (code "77") (name "unconnected-(U7-PC0-Pad8)") (class "Default")
      (node (ref "U7") (pin "8") (pinfunction "PC0_8") (pintype "passive+no_connect"))
    )
    (net (code "78") (name "unconnected-(U7-PC1-Pad9)") (class "Default")
      (node (ref "U7") (pin "9") (pinfunction "PC1_9") (pintype "passive+no_connect"))
    )
    (net (code "79") (name "unconnected-(U7-PC6-Pad37)") (class "Default")
      (node (ref "U7") (pin "37") (pinfunction "PC6_37") (pintype "passive+no_connect"))
    )
    (net (code "80") (name "unconnected-(U7-PC7-Pad38)") (class "Default")
      (node (ref "U7") (pin "38") (pinfunction "PC7_38") (pintype "passive+no_connect"))
    )
    (net (code "81") (name "unconnected-(U7-PC10-Pad51)") (class "Default")
      (node (ref "U7") (pin "51") (pinfunction "PC10_51") (pintype "passive+no_connect"))
    )
    (net (code "82") (name "unconnected-(U7-PC12-Pad53)") (class "Default")
      (node (ref "U7") (pin "53") (pinfunction "PC12_53") (pintype "passive+no_connect"))
    )
    (net (code "83") (name "unconnected-(U7-PC13-Pad2)") (class "Default")
      (node (ref "U7") (pin "2") (pinfunction "PC13_2") (pintype "passive+no_connect"))
    )
  )
)
